# versao4_0.net
KiCad netlist of a schematic drawn in EAGLE
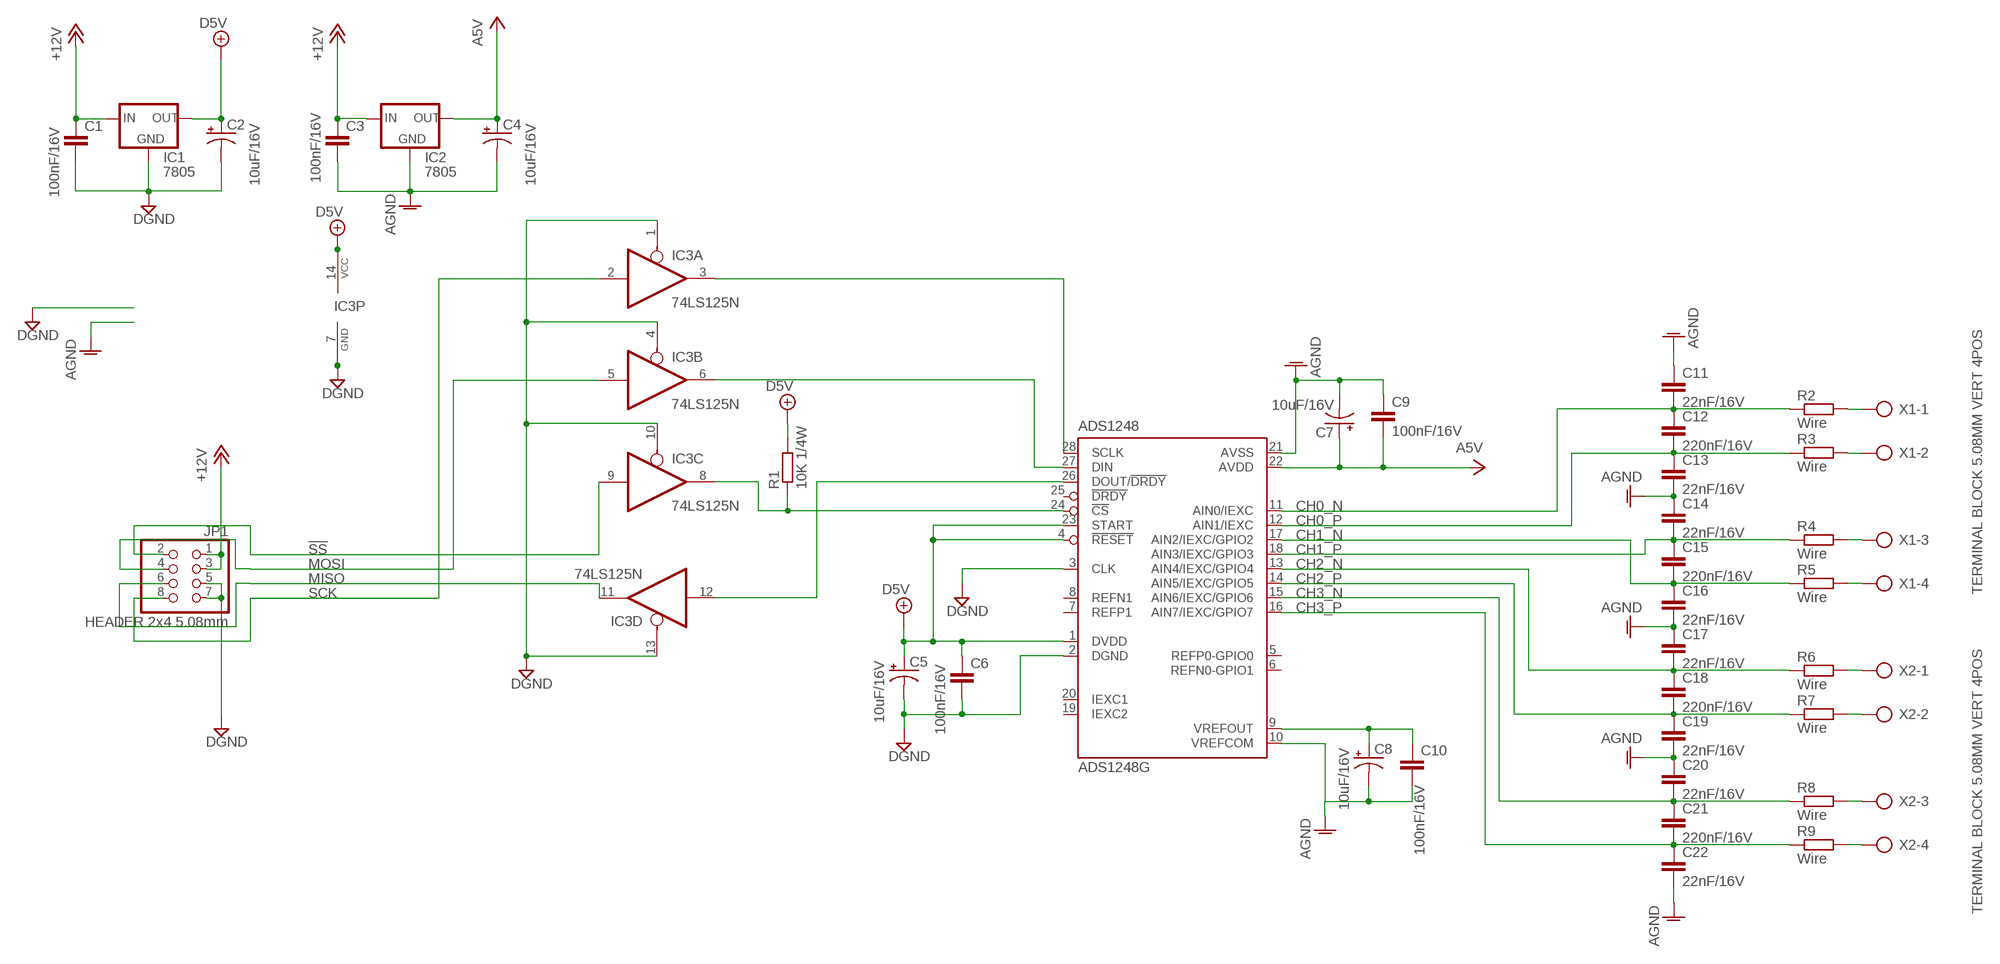
[diagram p0: schematic, sheet 1]

(export (version "E")
  (design (tool "Eeschema 10.0.6"))
  (components
    (comp (ref "C1")
      (value "100nF/16V")
      (footprint "eagle-import:C5B3")
      (libsource (lib "eagle-import") (part "C5/3"))
    )
    (comp (ref "C2")
      (value "10uF/16V")
      (footprint "eagle-import:E2-5")
      (libsource (lib "eagle-import") (part "CPOL-USE2-5"))
    )
    (comp (ref "C3")
      (value "100nF/16V")
      (footprint "eagle-import:C5B3")
      (libsource (lib "eagle-import") (part "C5/3"))
    )
    (comp (ref "C4")
      (value "10uF/16V")
      (footprint "eagle-import:E2-5")
      (libsource (lib "eagle-import") (part "CPOL-USE2-5"))
    )
    (comp (ref "C5")
      (value "10uF/16V")
      (footprint "eagle-import:E2-5")
      (libsource (lib "eagle-import") (part "CPOL-USE2-5"))
    )
    (comp (ref "C6")
      (value "100nF/16V")
      (footprint "eagle-import:C5B3")
      (libsource (lib "eagle-import") (part "C5/3"))
    )
    (comp (ref "C7")
      (value "10uF/16V")
      (footprint "eagle-import:E2-5")
      (libsource (lib "eagle-import") (part "CPOL-USE2-5"))
    )
    (comp (ref "C8")
      (value "10uF/16V")
      (footprint "eagle-import:E2-5")
      (libsource (lib "eagle-import") (part "CPOL-USE2-5"))
    )
    (comp (ref "C9")
      (value "100nF/16V")
      (footprint "eagle-import:C5B3")
      (libsource (lib "eagle-import") (part "C5/3"))
    )
    (comp (ref "C10")
      (value "100nF/16V")
      (footprint "eagle-import:C5B3")
      (libsource (lib "eagle-import") (part "C5/3"))
    )
    (comp (ref "C11")
      (value "22nF/16V")
      (footprint "eagle-import:C5B2.5")
      (libsource (lib "eagle-import") (part "C5/2.5"))
    )
    (comp (ref "C12")
      (value "220nF/16V")
      (footprint "eagle-import:C5B2.5")
      (libsource (lib "eagle-import") (part "C5/2.5"))
    )
    (comp (ref "C13")
      (value "22nF/16V")
      (footprint "eagle-import:C5B2.5")
      (libsource (lib "eagle-import") (part "C5/2.5"))
    )
    (comp (ref "C14")
      (value "22nF/16V")
      (footprint "eagle-import:C5B2.5")
      (libsource (lib "eagle-import") (part "C5/2.5"))
    )
    (comp (ref "C15")
      (value "220nF/16V")
      (footprint "eagle-import:C5B2.5")
      (libsource (lib "eagle-import") (part "C5/2.5"))
    )
    (comp (ref "C16")
      (value "22nF/16V")
      (footprint "eagle-import:C5B2.5")
      (libsource (lib "eagle-import") (part "C5/2.5"))
    )
    (comp (ref "C17")
      (value "22nF/16V")
      (footprint "eagle-import:C5B2.5")
      (libsource (lib "eagle-import") (part "C5/2.5"))
    )
    (comp (ref "C18")
      (value "220nF/16V")
      (footprint "eagle-import:C5B2.5")
      (libsource (lib "eagle-import") (part "C5/2.5"))
    )
    (comp (ref "C19")
      (value "22nF/16V")
      (footprint "eagle-import:C5B3")
      (libsource (lib "eagle-import") (part "C5/3"))
    )
    (comp (ref "C20")
      (value "22nF/16V")
      (footprint "eagle-import:C5B2.5")
      (libsource (lib "eagle-import") (part "C5/2.5"))
    )
    (comp (ref "C21")
      (value "220nF/16V")
      (footprint "eagle-import:C5B2.5")
      (libsource (lib "eagle-import") (part "C5/2.5"))
    )
    (comp (ref "C22")
      (value "22nF/16V")
      (footprint "eagle-import:C5B2.5")
      (libsource (lib "eagle-import") (part "C5/2.5"))
    )
    (comp (ref "IC1")
      (value "7805")
      (footprint "eagle-import:78XXL")
      (libsource (lib "eagle-import") (part "78XXL"))
    )
    (comp (ref "IC2")
      (value "7805")
      (footprint "eagle-import:78XXL")
      (libsource (lib "eagle-import") (part "78XXL"))
    )
    (comp (ref "IC3")
      (value "74LS125N")
      (footprint "eagle-import:DIL14")
      (libsource (lib "eagle-import") (part "74125NLS"))
    )
    (comp (ref "IC4")
      (value "ADS1248G")
      (footprint "eagle-import:P-TSSOP28-1")
      (libsource (lib "eagle-import") (part "ADS1248G"))
    )
    (comp (ref "JP1")
      (value "HEADER 2x4 5.08mm")
      (footprint "eagle-import:2X04")
      (libsource (lib "eagle-import") (part "PINHD-2X4"))
    )
    (comp (ref "R1")
      (value "10K 1/4W")
      (footprint "eagle-import:0204_7")
      (libsource (lib "eagle-import") (part "R-EU_0204/7"))
    )
    (comp (ref "R2")
      (value "Wire")
      (footprint "eagle-import:0204_7")
      (libsource (lib "eagle-import") (part "R-EU_0204/7"))
    )
    (comp (ref "R3")
      (value "Wire")
      (footprint "eagle-import:0204_7")
      (libsource (lib "eagle-import") (part "R-EU_0204/7"))
    )
    (comp (ref "R4")
      (value "Wire")
      (footprint "eagle-import:0204_7")
      (libsource (lib "eagle-import") (part "R-EU_0204/7"))
    )
    (comp (ref "R5")
      (value "Wire")
      (footprint "eagle-import:0204_7")
      (libsource (lib "eagle-import") (part "R-EU_0204/7"))
    )
    (comp (ref "R6")
      (value "Wire")
      (footprint "eagle-import:0204_7")
      (libsource (lib "eagle-import") (part "R-EU_0204/7"))
    )
    (comp (ref "R7")
      (value "Wire")
      (footprint "eagle-import:0204_7")
      (libsource (lib "eagle-import") (part "R-EU_0204/7"))
    )
    (comp (ref "R8")
      (value "Wire")
      (footprint "eagle-import:0204_7")
      (libsource (lib "eagle-import") (part "R-EU_0204/7"))
    )
    (comp (ref "R9")
      (value "Wire")
      (footprint "eagle-import:0204_7")
      (libsource (lib "eagle-import") (part "R-EU_0204/7"))
    )
    (comp (ref "X1")
      (value "TERMINAL BLOCK 5.08MM VERT 4POS")
      (footprint "eagle-import:AK500_4-H")
      (libsource (lib "eagle-import") (part "AK500/4-H"))
    )
    (comp (ref "X2")
      (value "TERMINAL BLOCK 5.08MM VERT 4POS")
      (footprint "eagle-import:AK500_4-H")
      (libsource (lib "eagle-import") (part "AK500/4-H"))
    )
  )
  (nets
    (net (code "1") (name "+12V") (class "Default")
      (node (ref "C1") (pin "1") (pinfunction "1_1") (pintype "passive"))
      (node (ref "C3") (pin "1") (pinfunction "1_1") (pintype "passive"))
      (node (ref "IC1") (pin "IN") (pinfunction "IN_IN") (pintype "input"))
      (node (ref "IC2") (pin "IN") (pinfunction "IN_IN") (pintype "input"))
      (node (ref "JP1") (pin "1") (pinfunction "1_1") (pintype "passive"))
      (node (ref "JP1") (pin "3") (pinfunction "3_3") (pintype "passive"))
    )
    (net (code "2") (name "/CH0_N") (class "Default")
      (node (ref "C11") (pin "2") (pinfunction "2_2") (pintype "passive"))
      (node (ref "C12") (pin "1") (pinfunction "1_1") (pintype "passive"))
      (node (ref "IC4") (pin "11") (pinfunction "AIN0/IEXC_11") (pintype "bidirectional"))
      (node (ref "R2") (pin "1") (pinfunction "1_1") (pintype "passive"))
    )
    (net (code "3") (name "/CH0_P") (class "Default")
      (node (ref "C12") (pin "2") (pinfunction "2_2") (pintype "passive"))
      (node (ref "C13") (pin "1") (pinfunction "1_1") (pintype "passive"))
      (node (ref "IC4") (pin "12") (pinfunction "AIN1/IEXC_12") (pintype "bidirectional"))
      (node (ref "R3") (pin "1") (pinfunction "1_1") (pintype "passive"))
    )
    (net (code "4") (name "/CH1_N") (class "Default")
      (node (ref "C15") (pin "2") (pinfunction "2_2") (pintype "passive"))
      (node (ref "C16") (pin "1") (pinfunction "1_1") (pintype "passive"))
      (node (ref "IC4") (pin "17") (pinfunction "AIN2/IEXC/GPIO2_17") (pintype "bidirectional"))
      (node (ref "R5") (pin "1") (pinfunction "1_1") (pintype "passive"))
    )
    (net (code "5") (name "/CH1_P") (class "Default")
      (node (ref "C14") (pin "2") (pinfunction "2_2") (pintype "passive"))
      (node (ref "C15") (pin "1") (pinfunction "1_1") (pintype "passive"))
      (node (ref "IC4") (pin "18") (pinfunction "AIN3/IEXC/GPIO3_18") (pintype "bidirectional"))
      (node (ref "R4") (pin "1") (pinfunction "1_1") (pintype "passive"))
    )
    (net (code "6") (name "/CH2_N") (class "Default")
      (node (ref "C17") (pin "2") (pinfunction "2_2") (pintype "passive"))
      (node (ref "C18") (pin "1") (pinfunction "1_1") (pintype "passive"))
      (node (ref "IC4") (pin "13") (pinfunction "AIN4/IEXC/GPIO4_13") (pintype "bidirectional"))
      (node (ref "R6") (pin "1") (pinfunction "1_1") (pintype "passive"))
    )
    (net (code "7") (name "/CH2_P") (class "Default")
      (node (ref "C18") (pin "2") (pinfunction "2_2") (pintype "passive"))
      (node (ref "C19") (pin "1") (pinfunction "1_1") (pintype "passive"))
      (node (ref "IC4") (pin "14") (pinfunction "AIN5/IEXC/GPIO5_14") (pintype "bidirectional"))
      (node (ref "R7") (pin "1") (pinfunction "1_1") (pintype "passive"))
    )
    (net (code "8") (name "/CH3_N") (class "Default")
      (node (ref "C20") (pin "2") (pinfunction "2_2") (pintype "passive"))
      (node (ref "C21") (pin "1") (pinfunction "1_1") (pintype "passive"))
      (node (ref "IC4") (pin "15") (pinfunction "AIN6/IEXC/GPIO6_15") (pintype "bidirectional"))
      (node (ref "R8") (pin "1") (pinfunction "1_1") (pintype "passive"))
    )
    (net (code "9") (name "/CH3_P") (class "Default")
      (node (ref "C21") (pin "2") (pinfunction "2_2") (pintype "passive"))
      (node (ref "C22") (pin "1") (pinfunction "1_1") (pintype "passive"))
      (node (ref "IC4") (pin "16") (pinfunction "AIN7/IEXC/GPIO7_16") (pintype "bidirectional"))
      (node (ref "R9") (pin "1") (pinfunction "1_1") (pintype "passive"))
    )
    (net (code "10") (name "/MISO") (class "Default")
      (node (ref "IC3") (pin "11") (pinfunction "O_11") (pintype "tri_state"))
      (node (ref "JP1") (pin "6") (pinfunction "6_6") (pintype "passive"))
    )
    (net (code "11") (name "/MOSI") (class "Default")
      (node (ref "IC3") (pin "5") (pinfunction "I_5") (pintype "input"))
      (node (ref "JP1") (pin "4") (pinfunction "4_4") (pintype "passive"))
    )
    (net (code "12") (name "/SCK") (class "Default")
      (node (ref "IC3") (pin "2") (pinfunction "I_2") (pintype "input"))
      (node (ref "JP1") (pin "8") (pinfunction "8_8") (pintype "passive"))
    )
    (net (code "13") (name "/~{SS}") (class "Default")
      (node (ref "IC3") (pin "9") (pinfunction "I_9") (pintype "input"))
      (node (ref "JP1") (pin "2") (pinfunction "2_2") (pintype "passive"))
    )
    (net (code "14") (name "A5V") (class "Default")
      (node (ref "C4") (pin "+") (pinfunction "+_+") (pintype "passive"))
      (node (ref "C7") (pin "+") (pinfunction "+_+") (pintype "passive"))
      (node (ref "C9") (pin "2") (pinfunction "2_2") (pintype "passive"))
      (node (ref "IC2") (pin "OUT") (pinfunction "OUT_OUT") (pintype "passive"))
      (node (ref "IC4") (pin "22") (pinfunction "AVDD_22") (pintype "input"))
    )
    (net (code "15") (name "AGND") (class "Default")
      (node (ref "C10") (pin "2") (pinfunction "2_2") (pintype "passive"))
      (node (ref "C11") (pin "1") (pinfunction "1_1") (pintype "passive"))
      (node (ref "C13") (pin "2") (pinfunction "2_2") (pintype "passive"))
      (node (ref "C14") (pin "1") (pinfunction "1_1") (pintype "passive"))
      (node (ref "C16") (pin "2") (pinfunction "2_2") (pintype "passive"))
      (node (ref "C17") (pin "1") (pinfunction "1_1") (pintype "passive"))
      (node (ref "C19") (pin "2") (pinfunction "2_2") (pintype "passive"))
      (node (ref "C20") (pin "1") (pinfunction "1_1") (pintype "passive"))
      (node (ref "C22") (pin "2") (pinfunction "2_2") (pintype "passive"))
      (node (ref "C3") (pin "2") (pinfunction "2_2") (pintype "passive"))
      (node (ref "C4") (pin "-") (pinfunction "-_-") (pintype "passive"))
      (node (ref "C7") (pin "-") (pinfunction "-_-") (pintype "passive"))
      (node (ref "C8") (pin "-") (pinfunction "-_-") (pintype "passive"))
      (node (ref "C9") (pin "1") (pinfunction "1_1") (pintype "passive"))
      (node (ref "IC2") (pin "GND") (pinfunction "GND_GND") (pintype "input"))
      (node (ref "IC4") (pin "10") (pinfunction "VREFCOM_10") (pintype "output"))
      (node (ref "IC4") (pin "21") (pinfunction "AVSS_21") (pintype "input"))
    )
    (net (code "16") (name "D5V") (class "Default")
      (node (ref "C2") (pin "+") (pinfunction "+_+") (pintype "passive"))
      (node (ref "C5") (pin "+") (pinfunction "+_+") (pintype "passive"))
      (node (ref "C6") (pin "1") (pinfunction "1_1") (pintype "passive"))
      (node (ref "IC1") (pin "OUT") (pinfunction "OUT_OUT") (pintype "passive"))
      (node (ref "IC3") (pin "14") (pinfunction "VCC_14") (pintype "power_in"))
      (node (ref "IC4") (pin "1") (pinfunction "DVDD_1") (pintype "input"))
      (node (ref "IC4") (pin "23") (pinfunction "START_23") (pintype "input"))
      (node (ref "IC4") (pin "4") (pinfunction "~{RESET}_4") (pintype "input"))
      (node (ref "R1") (pin "2") (pinfunction "2_2") (pintype "passive"))
    )
    (net (code "17") (name "DGND") (class "Default")
      (node (ref "C1") (pin "2") (pinfunction "2_2") (pintype "passive"))
      (node (ref "C2") (pin "-") (pinfunction "-_-") (pintype "passive"))
      (node (ref "C5") (pin "-") (pinfunction "-_-") (pintype "passive"))
      (node (ref "C6") (pin "2") (pinfunction "2_2") (pintype "passive"))
      (node (ref "IC1") (pin "GND") (pinfunction "GND_GND") (pintype "input"))
      (node (ref "IC3") (pin "1") (pinfunction "OE_1") (pintype "input"))
      (node (ref "IC3") (pin "10") (pinfunction "OE_10") (pintype "input"))
      (node (ref "IC3") (pin "13") (pinfunction "OE_13") (pintype "input"))
      (node (ref "IC3") (pin "4") (pinfunction "OE_4") (pintype "input"))
      (node (ref "IC3") (pin "7") (pinfunction "GND_7") (pintype "power_in"))
      (node (ref "IC4") (pin "2") (pinfunction "DGND_2") (pintype "input"))
      (node (ref "IC4") (pin "3") (pinfunction "CLK_3") (pintype "input"))
      (node (ref "JP1") (pin "5") (pinfunction "5_5") (pintype "passive"))
      (node (ref "JP1") (pin "7") (pinfunction "7_7") (pintype "passive"))
    )
    (net (code "18") (name "Net-(IC3A-O)") (class "Default")
      (node (ref "IC3") (pin "3") (pinfunction "O_3") (pintype "tri_state"))
      (node (ref "IC4") (pin "28") (pinfunction "SCLK_28") (pintype "input"))
    )
    (net (code "19") (name "Net-(IC3B-O)") (class "Default")
      (node (ref "IC3") (pin "6") (pinfunction "O_6") (pintype "tri_state"))
      (node (ref "IC4") (pin "27") (pinfunction "DIN_27") (pintype "input"))
    )
    (net (code "20") (name "Net-(IC3C-O)") (class "Default")
      (node (ref "IC3") (pin "8") (pinfunction "O_8") (pintype "tri_state"))
      (node (ref "IC4") (pin "24") (pinfunction "~{CS}_24") (pintype "input"))
      (node (ref "R1") (pin "1") (pinfunction "1_1") (pintype "passive"))
    )
    (net (code "21") (name "Net-(IC3D-I)") (class "Default")
      (node (ref "IC3") (pin "12") (pinfunction "I_12") (pintype "input"))
      (node (ref "IC4") (pin "26") (pinfunction "DOUT/~{DRDY}_26") (pintype "output"))
    )
    (net (code "22") (name "Net-(IC4-VREFOUT)") (class "Default")
      (node (ref "C10") (pin "1") (pinfunction "1_1") (pintype "passive"))
      (node (ref "C8") (pin "+") (pinfunction "+_+") (pintype "passive"))
      (node (ref "IC4") (pin "9") (pinfunction "VREFOUT_9") (pintype "output"))
    )
    (net (code "23") (name "Net-(X1A-KL)") (class "Default")
      (node (ref "R2") (pin "2") (pinfunction "2_2") (pintype "passive"))
      (node (ref "X1") (pin "1") (pinfunction "KL_1") (pintype "passive"))
    )
    (net (code "24") (name "Net-(X1B-KL)") (class "Default")
      (node (ref "R3") (pin "2") (pinfunction "2_2") (pintype "passive"))
      (node (ref "X1") (pin "2") (pinfunction "KL_2") (pintype "passive"))
    )
    (net (code "25") (name "Net-(X1C-KL)") (class "Default")
      (node (ref "R4") (pin "2") (pinfunction "2_2") (pintype "passive"))
      (node (ref "X1") (pin "3") (pinfunction "KL_3") (pintype "passive"))
    )
    (net (code "26") (name "Net-(X1D-KL)") (class "Default")
      (node (ref "R5") (pin "2") (pinfunction "2_2") (pintype "passive"))
      (node (ref "X1") (pin "4") (pinfunction "KL_4") (pintype "passive"))
    )
    (net (code "27") (name "Net-(X2A-KL)") (class "Default")
      (node (ref "R6") (pin "2") (pinfunction "2_2") (pintype "passive"))
      (node (ref "X2") (pin "1") (pinfunction "KL_1") (pintype "passive"))
    )
    (net (code "28") (name "Net-(X2B-KL)") (class "Default")
      (node (ref "R7") (pin "2") (pinfunction "2_2") (pintype "passive"))
      (node (ref "X2") (pin "2") (pinfunction "KL_2") (pintype "passive"))
    )
    (net (code "29") (name "Net-(X2C-KL)") (class "Default")
      (node (ref "R8") (pin "2") (pinfunction "2_2") (pintype "passive"))
      (node (ref "X2") (pin "3") (pinfunction "KL_3") (pintype "passive"))
    )
    (net (code "30") (name "Net-(X2D-KL)") (class "Default")
      (node (ref "R9") (pin "2") (pinfunction "2_2") (pintype "passive"))
      (node (ref "X2") (pin "4") (pinfunction "KL_4") (pintype "passive"))
    )
    (net (code "31") (name "unconnected-(IC4-IEXC1-Pad20)") (class "Default")
      (node (ref "IC4") (pin "20") (pinfunction "IEXC1_20") (pintype "output"))
    )
    (net (code "32") (name "unconnected-(IC4-IEXC2-Pad19)") (class "Default")
      (node (ref "IC4") (pin "19") (pinfunction "IEXC2_19") (pintype "output"))
    )
    (net (code "33") (name "unconnected-(IC4-REFN0-GPIO1-Pad6)") (class "Default")
      (node (ref "IC4") (pin "6") (pinfunction "REFN0-GPIO1_6") (pintype "bidirectional"))
    )
    (net (code "34") (name "unconnected-(IC4-REFN1-Pad8)") (class "Default")
      (node (ref "IC4") (pin "8") (pinfunction "REFN1_8") (pintype "bidirectional"))
    )
    (net (code "35") (name "unconnected-(IC4-REFP0-GPIO0-Pad5)") (class "Default")
      (node (ref "IC4") (pin "5") (pinfunction "REFP0-GPIO0_5") (pintype "bidirectional"))
    )
    (net (code "36") (name "unconnected-(IC4-REFP1-Pad7)") (class "Default")
      (node (ref "IC4") (pin "7") (pinfunction "REFP1_7") (pintype "bidirectional"))
    )
    (net (code "37") (name "unconnected-(IC4-~{DRDY}-Pad25)") (class "Default")
      (node (ref "IC4") (pin "25") (pinfunction "~{DRDY}_25") (pintype "output"))
    )
  )
)
